# 19VBuck_Polygon_Pour.net
KiCad netlist of a schematic drawn in Altium Designer
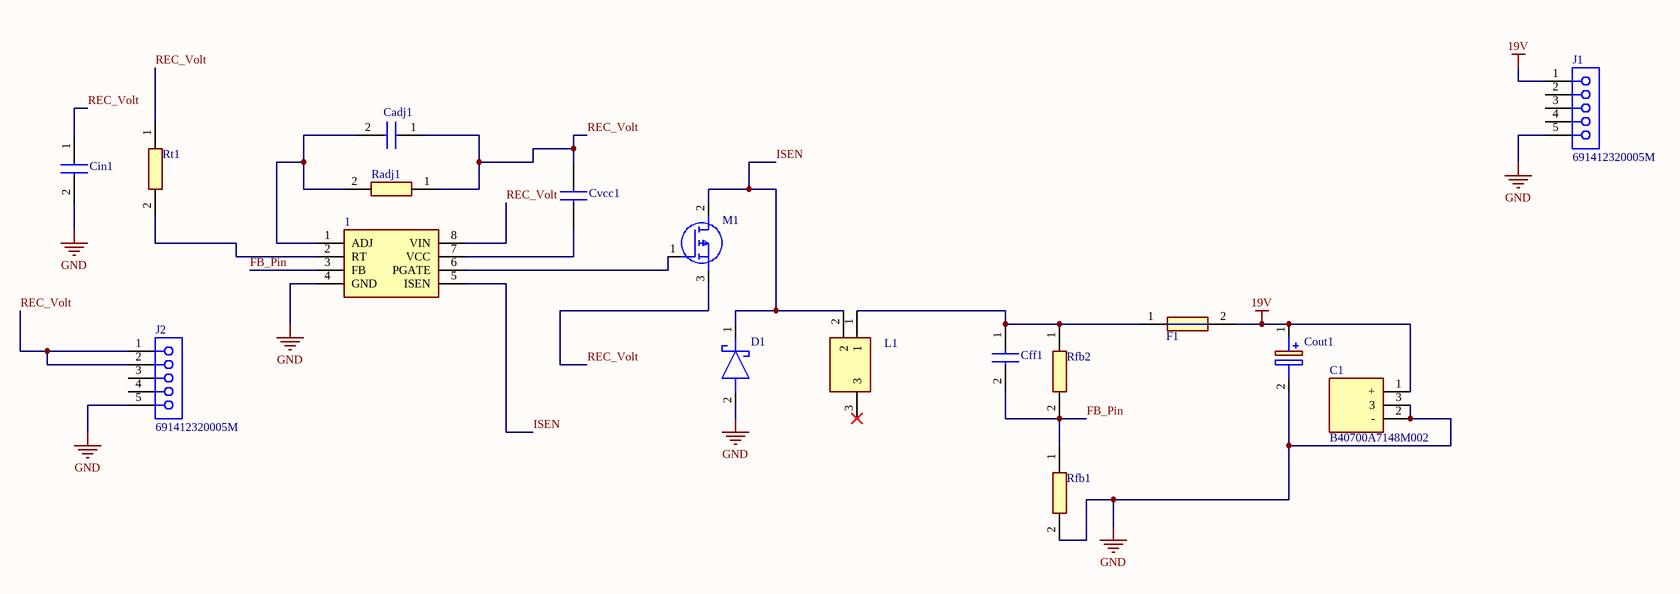
[diagram p0: 19VBuck_Polygon_Pour.SchDoc]

(export (version "E")
  (design (tool "Eeschema 10.0.6"))
  (components
    (comp (ref "1")
      (value "LM25085AMM_NOPB")
      (footprint "SamacSys:SOP65P490X110-8N")
      (description "Integrated Circuit")
      (fields
        (field (name "MANUFACTURER_PART_NUMBER") "LM25085AMM/NOPB")
        (field (name "MOUSER PART NUMBER") "926-LM25085AMM/NOPB")
      )
      (libsource (lib "*") (part "LM25085AMM_NOPB"))
    )
    (comp (ref "C1")
      (value "B40700A7148M002")
      (footprint "SamacSys:B40700A7148M002")
      (description "Capacitor Polarised")
      (libsource (lib "*") (part "B40700A7148M002"))
    )
    (comp (ref "Cadj1")
      (value "C1206C102K5GACTU")
      (footprint "SamacSys:C1206")
      (description "Capacitor")
      (libsource (lib "*") (part "C1206C102K5GACTU"))
    )
    (comp (ref "Cff1")
      (value "~")
      (footprint "SamacSys:C1206")
      (description "Capacitor")
      (fields
        (field (name "MANUFACTURER_PART_NUMBER") "C1206C333K5RACTU")
        (field (name "MOUSER PART NUMBER") "80-C1206C333K5R")
      )
      (libsource (lib "*") (part "C1206C333K5RACTU"))
    )
    (comp (ref "Cin1")
      (value "MSASU32MSB5106KPNA01")
      (footprint "SamacSys:CAPC3225X270N")
      (description "Capacitor")
      (libsource (lib "*") (part "MSASU32MSB5106KPNA01"))
    )
    (comp (ref "Cout1")
      (value "293D106X9063E2TE3")
      (footprint "SamacSys:CAPPM7343X430N")
      (description "Capacitor Polarised")
      (fields (field (name "MOUSER PART NUMBER") "74-293D106X9063E2TE3"))
      (libsource (lib "*") (part "293D106X9063E2TE3"))
    )
    (comp (ref "Cvcc1")
      (value "TMK212BJ474KD-T")
      (footprint "CAPC2012X95N")
      (description "TAIYO YUDEN - TMK212BJ474KD-T - CERAMIC CAPACITOR 0.47UF, 25V, X5R, 10%, 0805")
      (fields (field (name "MOUSER PART NUMBER") "963-TMK212BJ474KD-T"))
      (libsource (lib "TMK212BJ474KD-T") (part "TMK212BJ474KD-T"))
    )
    (comp (ref "D1")
      (value "SS24FL")
      (footprint "SamacSys:SODFL3617X108N")
      (description "Schottky Diode")
      (fields (field (name "MOUSER PART NUMBER") "512-SS24FL"))
      (libsource (lib "*") (part "SS24FL"))
    )
    (comp (ref "F1")
      (value "0407006.WR")
      (footprint "SamacSys:FUSC3216X98N")
      (description "Fuse")
      (fields (field (name "MOUSER PART NUMBER") "576-0407006.WR"))
      (libsource (lib "*") (part "0407006.WR"))
    )
    (comp (ref "J1")
      (value "691412320005M")
      (footprint "691412320005M")
      (description "Terminal Block, 3.81MM Pitch, 45 Deg, Screwless, 16 -30 AWG, 5 Pins")
      (libsource (lib "Altium Content Vault") (part "TBL - 1R - 05P - Female"))
    )
    (comp (ref "J2")
      (value "691412320005M")
      (footprint "691412320005M")
      (description "Terminal Block, 3.81MM Pitch, 45 Deg, Screwless, 16 -30 AWG, 5 Pins")
      (libsource (lib "Altium Content Vault") (part "TBL - 1R - 05P - Female"))
    )
    (comp (ref "L1")
      (value "SER2915L-153KL")
      (footprint "SamacSys:SER2918H333KL")
      (description "Inductor")
      (fields (field (name "MOUSER PART NUMBER") "994-SER2915L-153KL"))
      (libsource (lib "*") (part "SER2915L-153KL"))
    )
    (comp (ref "M1")
      (value "SUD50P04-08-GE3")
      (footprint "SamacSys:SIHD3N50DT4GE3")
      (description "MOSFET (P-Channel)")
      (fields (field (name "MOUSER PART NUMBER") "781-SUD50P04-08-GE3"))
      (libsource (lib "*") (part "SUD50P04-08-GE3"))
    )
    (comp (ref "Radj1")
      (value "CRCW12062K21FKEA")
      (footprint "SamacSys:RESC3216X60N")
      (description "Resistor")
      (fields (field (name "MOUSER PART NUMBER") "71-CRCW1206-2.21K-E3"))
      (libsource (lib "*") (part "CRCW12062K21FKEA"))
    )
    (comp (ref "Rfb1")
      (value "CRCW1206499RFKEA")
      (footprint "SamacSys:RESC3216X60N")
      (description "Resistor")
      (fields (field (name "MOUSER PART NUMBER") "71-CRCW1206-499-E3"))
      (libsource (lib "*") (part "CRCW1206499RFKEA"))
    )
    (comp (ref "Rfb2")
      (value "RC1206FR-0710KL")
      (footprint "SamacSys:RESC3116X65N")
      (description "Resistor")
      (fields (field (name "MOUSER PART NUMBER") "603-RC1206FR-0710KL"))
      (libsource (lib "*") (part "RC1206FR-0710KL"))
    )
    (comp (ref "Rt1")
      (value "CRCW1206665KFKEA")
      (footprint "SamacSys:RESC3216X60N")
      (description "Resistor")
      (libsource (lib "*") (part "CRCW1206665KFKEA"))
    )
  )
  (nets
    (net (code "1") (name "/FB_Pin") (class "Default")
      (node (ref "1") (pin "3") (pinfunction "FB_3") (pintype "passive"))
      (node (ref "Cff1") (pin "2") (pinfunction "2_2") (pintype "passive"))
      (node (ref "Rfb1") (pin "1") (pinfunction "1_1") (pintype "passive"))
      (node (ref "Rfb2") (pin "2") (pinfunction "2_2") (pintype "passive"))
    )
    (net (code "2") (name "/ISEN") (class "Default")
      (node (ref "1") (pin "5") (pinfunction "ISEN_5") (pintype "passive"))
      (node (ref "D1") (pin "1") (pinfunction "K_1") (pintype "passive"))
      (node (ref "L1") (pin "2") (pinfunction "2_2") (pintype "passive"))
      (node (ref "M1") (pin "2") (pinfunction "D_2") (pintype "passive"))
    )
    (net (code "3") (name "/REC_Volt") (class "Default")
      (node (ref "1") (pin "8") (pinfunction "VIN_8") (pintype "passive"))
      (node (ref "Cadj1") (pin "1") (pinfunction "1_1") (pintype "passive"))
      (node (ref "Cin1") (pin "1") (pinfunction "1_1") (pintype "passive"))
      (node (ref "Cvcc1") (pin "2") (pinfunction "2_2") (pintype "passive"))
      (node (ref "J2") (pin "1") (pinfunction "1_1") (pintype "passive"))
      (node (ref "J2") (pin "2") (pinfunction "2_2") (pintype "passive"))
      (node (ref "M1") (pin "3") (pinfunction "S_3") (pintype "passive"))
      (node (ref "Radj1") (pin "1") (pinfunction "1_1") (pintype "passive"))
      (node (ref "Rt1") (pin "1") (pinfunction "1_1") (pintype "passive"))
    )
    (net (code "4") (name "19V") (class "Default")
      (node (ref "C1") (pin "1") (pinfunction "+_1") (pintype "passive"))
      (node (ref "Cout1") (pin "1") (pinfunction "+_1") (pintype "passive"))
      (node (ref "F1") (pin "2") (pinfunction "2_2") (pintype "passive"))
      (node (ref "J1") (pin "1") (pinfunction "1_1") (pintype "passive"))
    )
    (net (code "5") (name "GND") (class "Default")
      (node (ref "1") (pin "4") (pinfunction "GND_4") (pintype "passive"))
      (node (ref "C1") (pin "2") (pinfunction "-_2") (pintype "passive"))
      (node (ref "C1") (pin "3") (pinfunction "3_3") (pintype "passive"))
      (node (ref "Cin1") (pin "2") (pinfunction "2_2") (pintype "passive"))
      (node (ref "Cout1") (pin "2") (pinfunction "-_2") (pintype "passive"))
      (node (ref "D1") (pin "2") (pinfunction "A_2") (pintype "passive"))
      (node (ref "J1") (pin "5") (pinfunction "5_5") (pintype "passive"))
      (node (ref "J2") (pin "5") (pinfunction "5_5") (pintype "passive"))
      (node (ref "Rfb1") (pin "2") (pinfunction "2_2") (pintype "passive"))
    )
    (net (code "6") (name "Net-(1-ADJ)") (class "Default")
      (node (ref "1") (pin "1") (pinfunction "ADJ_1") (pintype "passive"))
      (node (ref "Cadj1") (pin "2") (pinfunction "2_2") (pintype "passive"))
      (node (ref "Radj1") (pin "2") (pinfunction "2_2") (pintype "passive"))
    )
    (net (code "7") (name "Net-(1-PGATE)") (class "Default")
      (node (ref "1") (pin "6") (pinfunction "PGATE_6") (pintype "passive"))
      (node (ref "M1") (pin "1") (pinfunction "G_1") (pintype "passive"))
    )
    (net (code "8") (name "Net-(1-RT)") (class "Default")
      (node (ref "1") (pin "2") (pinfunction "RT_2") (pintype "passive"))
      (node (ref "Rt1") (pin "2") (pinfunction "2_2") (pintype "passive"))
    )
    (net (code "9") (name "Net-(1-VCC)") (class "Default")
      (node (ref "1") (pin "7") (pinfunction "VCC_7") (pintype "passive"))
      (node (ref "Cvcc1") (pin "1") (pinfunction "1_1") (pintype "passive"))
    )
    (net (code "10") (name "Net-(Cff1-Pad1)") (class "Default")
      (node (ref "Cff1") (pin "1") (pinfunction "1_1") (pintype "passive"))
      (node (ref "F1") (pin "1") (pinfunction "1_1") (pintype "passive"))
      (node (ref "L1") (pin "1") (pinfunction "1_1") (pintype "passive"))
      (node (ref "Rfb2") (pin "1") (pinfunction "1_1") (pintype "passive"))
    )
    (net (code "11") (name "unconnected-(J1-Pad2)") (class "Default")
      (node (ref "J1") (pin "2") (pinfunction "2_2") (pintype "passive"))
    )
    (net (code "12") (name "unconnected-(J1-Pad3)") (class "Default")
      (node (ref "J1") (pin "3") (pinfunction "3_3") (pintype "passive"))
    )
    (net (code "13") (name "unconnected-(J1-Pad4)") (class "Default")
      (node (ref "J1") (pin "4") (pinfunction "4_4") (pintype "passive"))
    )
    (net (code "14") (name "unconnected-(J2-Pad3)") (class "Default")
      (node (ref "J2") (pin "3") (pinfunction "3_3") (pintype "passive"))
    )
    (net (code "15") (name "unconnected-(J2-Pad4)") (class "Default")
      (node (ref "J2") (pin "4") (pinfunction "4_4") (pintype "passive"))
    )
    (net (code "16") (name "unconnected-(L1-Pad3)") (class "Default")
      (node (ref "L1") (pin "3") (pinfunction "3_3") (pintype "passive+no_connect"))
    )
  )
)
